# onionboard.net
KiCad netlist of a schematic drawn in EAGLE
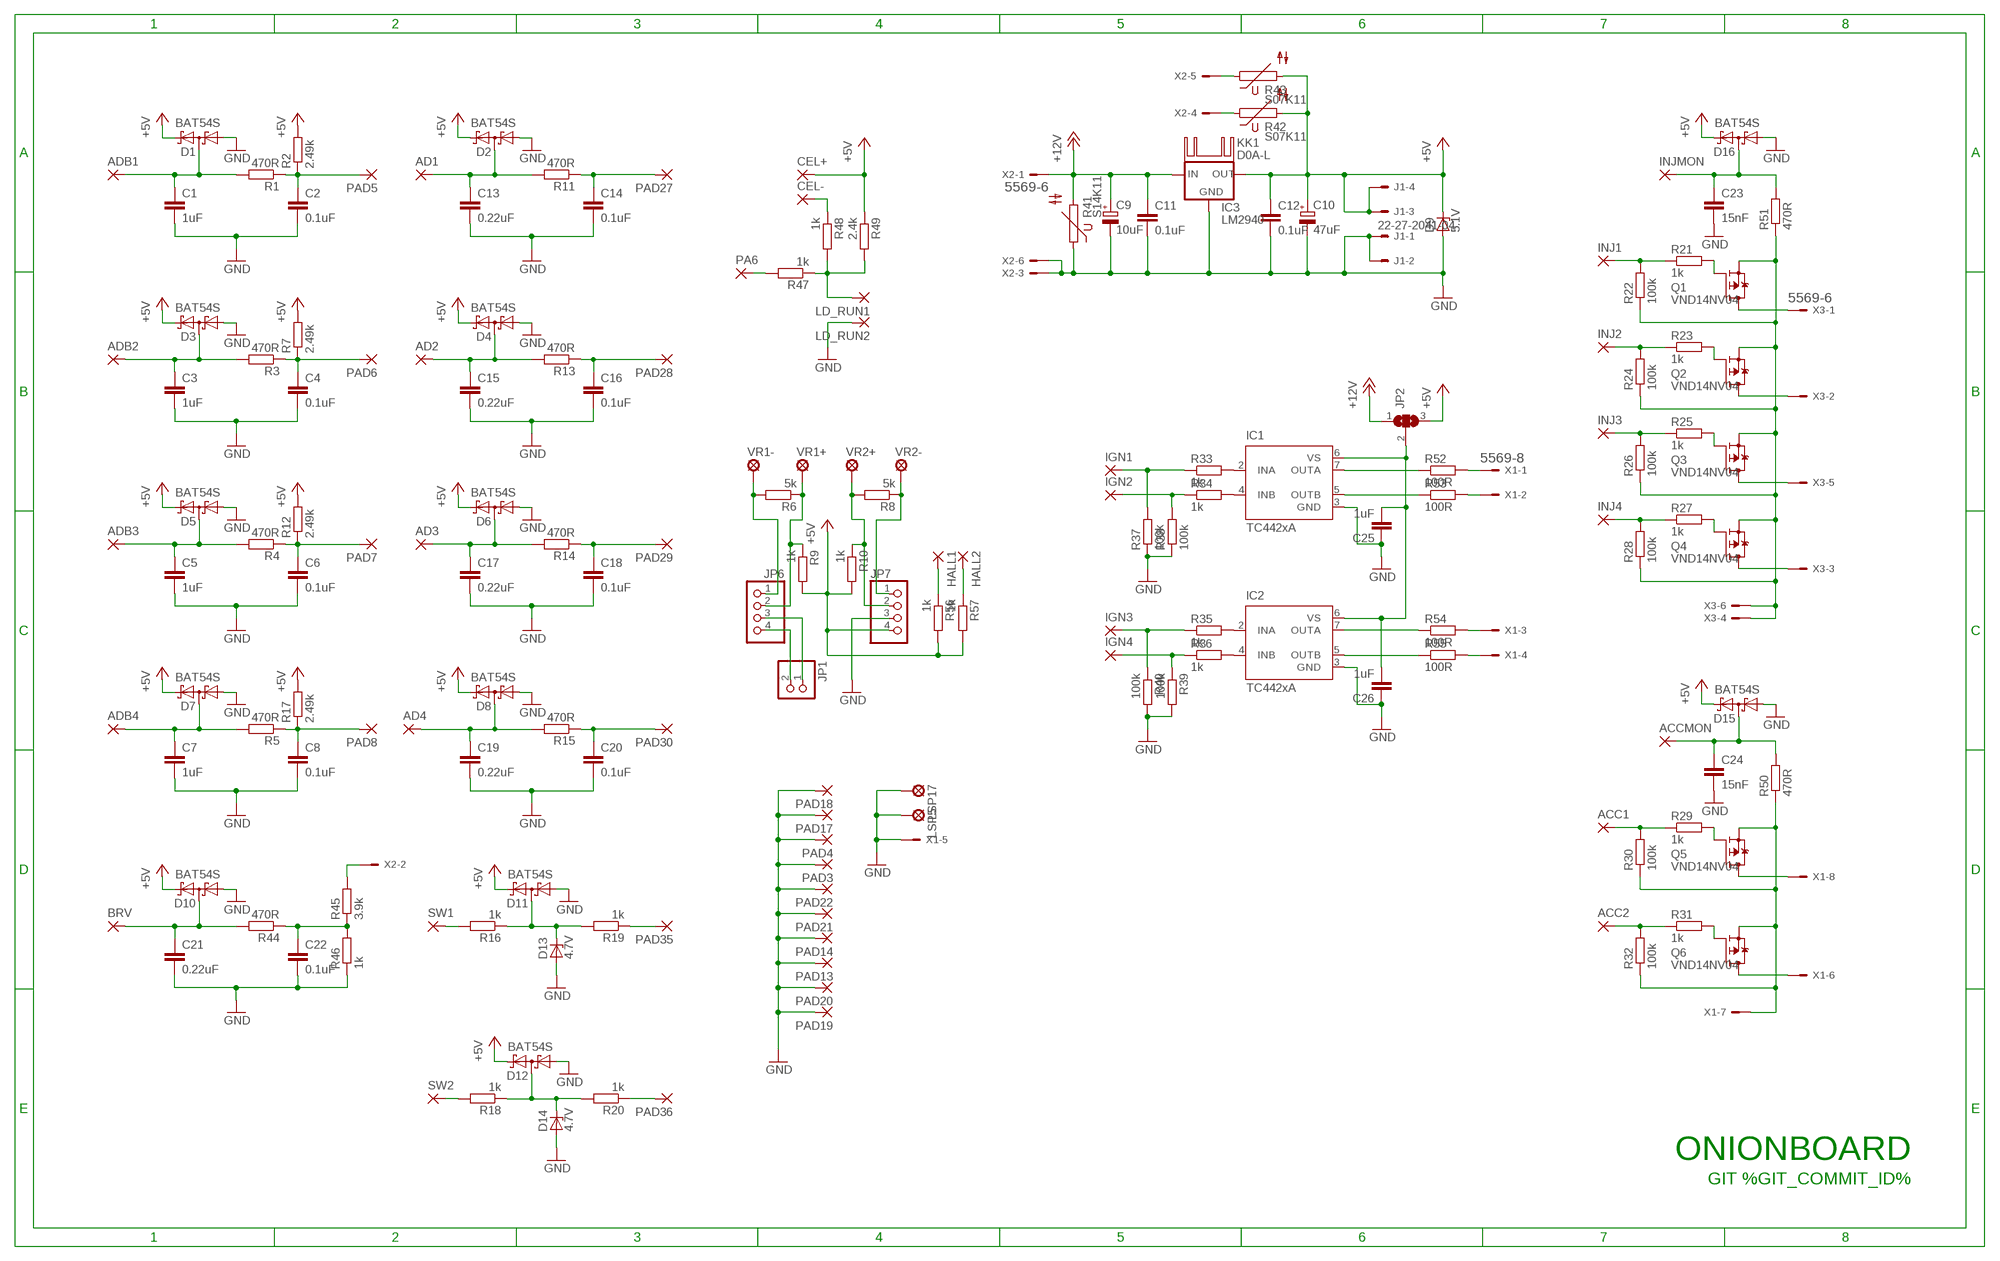
[diagram p0: schematic, sheet 1]

(export (version "E")
  (design (tool "Eeschema 10.0.6"))
  (components
    (comp (ref "ACC1")
      (value "SMD2")
      (footprint "eagle-import:SMD1,27-2,54")
      (libsource (lib "eagle-import") (part "SMD2"))
    )
    (comp (ref "ACC2")
      (value "SMD2")
      (footprint "eagle-import:SMD1,27-2,54")
      (libsource (lib "eagle-import") (part "SMD2"))
    )
    (comp (ref "ACCMON")
      (value "SMD2")
      (footprint "eagle-import:SMD1,27-2,54")
      (libsource (lib "eagle-import") (part "SMD2"))
    )
    (comp (ref "AD1")
      (value "SMD2")
      (footprint "eagle-import:SMD1,27-2,54")
      (libsource (lib "eagle-import") (part "SMD2"))
    )
    (comp (ref "AD2")
      (value "SMD2")
      (footprint "eagle-import:SMD1,27-2,54")
      (libsource (lib "eagle-import") (part "SMD2"))
    )
    (comp (ref "AD3")
      (value "SMD2")
      (footprint "eagle-import:SMD1,27-2,54")
      (libsource (lib "eagle-import") (part "SMD2"))
    )
    (comp (ref "AD4")
      (value "SMD2")
      (footprint "eagle-import:SMD1,27-2,54")
      (libsource (lib "eagle-import") (part "SMD2"))
    )
    (comp (ref "ADB1")
      (value "SMD2")
      (footprint "eagle-import:SMD1,27-2,54")
      (libsource (lib "eagle-import") (part "SMD2"))
    )
    (comp (ref "ADB2")
      (value "SMD2")
      (footprint "eagle-import:SMD1,27-2,54")
      (libsource (lib "eagle-import") (part "SMD2"))
    )
    (comp (ref "ADB3")
      (value "SMD2")
      (footprint "eagle-import:SMD1,27-2,54")
      (libsource (lib "eagle-import") (part "SMD2"))
    )
    (comp (ref "ADB4")
      (value "SMD2")
      (footprint "eagle-import:SMD1,27-2,54")
      (libsource (lib "eagle-import") (part "SMD2"))
    )
    (comp (ref "BRV")
      (value "SMD2")
      (footprint "eagle-import:SMD1,27-2,54")
      (libsource (lib "eagle-import") (part "SMD2"))
    )
    (comp (ref "C1")
      (value "1uF")
      (footprint "eagle-import:C0805")
      (libsource (lib "eagle-import") (part "C-EUC0805"))
    )
    (comp (ref "C2")
      (value "0.1uF")
      (footprint "eagle-import:C0805")
      (libsource (lib "eagle-import") (part "C-EUC0805"))
    )
    (comp (ref "C3")
      (value "1uF")
      (footprint "eagle-import:C0805")
      (libsource (lib "eagle-import") (part "C-EUC0805"))
    )
    (comp (ref "C4")
      (value "0.1uF")
      (footprint "eagle-import:C0805")
      (libsource (lib "eagle-import") (part "C-EUC0805"))
    )
    (comp (ref "C5")
      (value "1uF")
      (footprint "eagle-import:C0805")
      (libsource (lib "eagle-import") (part "C-EUC0805"))
    )
    (comp (ref "C6")
      (value "0.1uF")
      (footprint "eagle-import:C0805")
      (libsource (lib "eagle-import") (part "C-EUC0805"))
    )
    (comp (ref "C7")
      (value "1uF")
      (footprint "eagle-import:C0805")
      (libsource (lib "eagle-import") (part "C-EUC0805"))
    )
    (comp (ref "C8")
      (value "0.1uF")
      (footprint "eagle-import:C0805")
      (libsource (lib "eagle-import") (part "C-EUC0805"))
    )
    (comp (ref "C9")
      (value "10uF")
      (footprint "eagle-import:SMC_E")
      (libsource (lib "eagle-import") (part "CPOL-EUSMCE"))
    )
    (comp (ref "C10")
      (value "47uF")
      (footprint "eagle-import:SMC_E")
      (libsource (lib "eagle-import") (part "CPOL-EUSMCE"))
    )
    (comp (ref "C11")
      (value "0.1uF")
      (footprint "eagle-import:C1206")
      (libsource (lib "eagle-import") (part "C-EUC1206"))
    )
    (comp (ref "C12")
      (value "0.1uF")
      (footprint "eagle-import:C1206")
      (libsource (lib "eagle-import") (part "C-EUC1206"))
    )
    (comp (ref "C13")
      (value "0.22uF")
      (footprint "eagle-import:C0805")
      (libsource (lib "eagle-import") (part "C-EUC0805"))
    )
    (comp (ref "C14")
      (value "0.1uF")
      (footprint "eagle-import:C0805")
      (libsource (lib "eagle-import") (part "C-EUC0805"))
    )
    (comp (ref "C15")
      (value "0.22uF")
      (footprint "eagle-import:C0805")
      (libsource (lib "eagle-import") (part "C-EUC0805"))
    )
    (comp (ref "C16")
      (value "0.1uF")
      (footprint "eagle-import:C0805")
      (libsource (lib "eagle-import") (part "C-EUC0805"))
    )
    (comp (ref "C17")
      (value "0.22uF")
      (footprint "eagle-import:C0805")
      (libsource (lib "eagle-import") (part "C-EUC0805"))
    )
    (comp (ref "C18")
      (value "0.1uF")
      (footprint "eagle-import:C0805")
      (libsource (lib "eagle-import") (part "C-EUC0805"))
    )
    (comp (ref "C19")
      (value "0.22uF")
      (footprint "eagle-import:C0805")
      (libsource (lib "eagle-import") (part "C-EUC0805"))
    )
    (comp (ref "C20")
      (value "0.1uF")
      (footprint "eagle-import:C0805")
      (libsource (lib "eagle-import") (part "C-EUC0805"))
    )
    (comp (ref "C21")
      (value "0.22uF")
      (footprint "eagle-import:C0805")
      (libsource (lib "eagle-import") (part "C-EUC0805"))
    )
    (comp (ref "C22")
      (value "0.1uF")
      (footprint "eagle-import:C0805")
      (libsource (lib "eagle-import") (part "C-EUC0805"))
    )
    (comp (ref "C23")
      (value "15nF")
      (footprint "eagle-import:C0805")
      (libsource (lib "eagle-import") (part "C-EUC0805"))
    )
    (comp (ref "C24")
      (value "15nF")
      (footprint "eagle-import:C0805")
      (libsource (lib "eagle-import") (part "C-EUC0805"))
    )
    (comp (ref "C25")
      (value "1uF")
      (footprint "eagle-import:C1206")
      (libsource (lib "eagle-import") (part "C-EUC1206"))
    )
    (comp (ref "C26")
      (value "1uF")
      (footprint "eagle-import:C1206")
      (libsource (lib "eagle-import") (part "C-EUC1206"))
    )
    (comp (ref "CEL+")
      (value "SMD2")
      (footprint "eagle-import:SMD1,27-2,54")
      (libsource (lib "eagle-import") (part "SMD2"))
    )
    (comp (ref "CEL-")
      (value "SMD2")
      (footprint "eagle-import:SMD1,27-2,54")
      (libsource (lib "eagle-import") (part "SMD2"))
    )
    (comp (ref "D1")
      (value "BAT54S")
      (footprint "eagle-import:SOT23")
      (libsource (lib "eagle-import") (part "BAT54S"))
    )
    (comp (ref "D2")
      (value "BAT54S")
      (footprint "eagle-import:SOT23")
      (libsource (lib "eagle-import") (part "BAT54S"))
    )
    (comp (ref "D3")
      (value "BAT54S")
      (footprint "eagle-import:SOT23")
      (libsource (lib "eagle-import") (part "BAT54S"))
    )
    (comp (ref "D4")
      (value "BAT54S")
      (footprint "eagle-import:SOT23")
      (libsource (lib "eagle-import") (part "BAT54S"))
    )
    (comp (ref "D5")
      (value "BAT54S")
      (footprint "eagle-import:SOT23")
      (libsource (lib "eagle-import") (part "BAT54S"))
    )
    (comp (ref "D6")
      (value "BAT54S")
      (footprint "eagle-import:SOT23")
      (libsource (lib "eagle-import") (part "BAT54S"))
    )
    (comp (ref "D7")
      (value "BAT54S")
      (footprint "eagle-import:SOT23")
      (libsource (lib "eagle-import") (part "BAT54S"))
    )
    (comp (ref "D8")
      (value "BAT54S")
      (footprint "eagle-import:SOT23")
      (libsource (lib "eagle-import") (part "BAT54S"))
    )
    (comp (ref "D9")
      (value "5.1V")
      (footprint "eagle-import:P1Z12")
      (libsource (lib "eagle-import") (part "ZENER-DIODEP1-12"))
    )
    (comp (ref "D10")
      (value "BAT54S")
      (footprint "eagle-import:SOT23")
      (libsource (lib "eagle-import") (part "BAT54S"))
    )
    (comp (ref "D11")
      (value "BAT54S")
      (footprint "eagle-import:SOT23")
      (libsource (lib "eagle-import") (part "BAT54S"))
    )
    (comp (ref "D12")
      (value "BAT54S")
      (footprint "eagle-import:SOT23")
      (libsource (lib "eagle-import") (part "BAT54S"))
    )
    (comp (ref "D13")
      (value "4.7V")
      (footprint "eagle-import:SOT23")
      (libsource (lib "eagle-import") (part "ZENER-DIODESOT23"))
    )
    (comp (ref "D14")
      (value "4.7V")
      (footprint "eagle-import:SOT23")
      (libsource (lib "eagle-import") (part "ZENER-DIODESOT23"))
    )
    (comp (ref "D15")
      (value "BAT54S")
      (footprint "eagle-import:SOT23")
      (libsource (lib "eagle-import") (part "BAT54S"))
    )
    (comp (ref "D16")
      (value "BAT54S")
      (footprint "eagle-import:SOT23")
      (libsource (lib "eagle-import") (part "BAT54S"))
    )
    (comp (ref "HALL1")
      (value "1,6/0,8")
      (footprint "eagle-import:1,6_0,8")
      (libsource (lib "eagle-import") (part "1,6/0,8"))
    )
    (comp (ref "HALL2")
      (value "1,6/0,8")
      (footprint "eagle-import:1,6_0,8")
      (libsource (lib "eagle-import") (part "1,6/0,8"))
    )
    (comp (ref "IC1")
      (value "TC442xA")
      (footprint "eagle-import:SO08")
      (fields (field (name "MF") "INTERNATIONAL RECTIFIER(IR)") (field (name "MPN") "IR4427STRPBF"))
      (libsource (lib "eagle-import") (part "IR4427S"))
    )
    (comp (ref "IC2")
      (value "TC442xA")
      (footprint "eagle-import:SO08")
      (fields (field (name "MF") "INTERNATIONAL RECTIFIER(IR)") (field (name "MPN") "IR4427STRPBF"))
      (libsource (lib "eagle-import") (part "IR4427S"))
    )
    (comp (ref "IC3")
      (value "LM2940")
      (footprint "eagle-import:78XXL")
      (libsource (lib "eagle-import") (part "78XXL"))
    )
    (comp (ref "IGN1")
      (value "SMD2")
      (footprint "eagle-import:SMD1,27-2,54")
      (libsource (lib "eagle-import") (part "SMD2"))
    )
    (comp (ref "IGN2")
      (value "SMD2")
      (footprint "eagle-import:SMD1,27-2,54")
      (libsource (lib "eagle-import") (part "SMD2"))
    )
    (comp (ref "IGN3")
      (value "SMD2")
      (footprint "eagle-import:SMD1,27-2,54")
      (libsource (lib "eagle-import") (part "SMD2"))
    )
    (comp (ref "IGN4")
      (value "SMD2")
      (footprint "eagle-import:SMD1,27-2,54")
      (libsource (lib "eagle-import") (part "SMD2"))
    )
    (comp (ref "INJ1")
      (value "SMD2")
      (footprint "eagle-import:SMD1,27-2,54")
      (libsource (lib "eagle-import") (part "SMD2"))
    )
    (comp (ref "INJ2")
      (value "SMD2")
      (footprint "eagle-import:SMD1,27-2,54")
      (libsource (lib "eagle-import") (part "SMD2"))
    )
    (comp (ref "INJ3")
      (value "SMD2")
      (footprint "eagle-import:SMD1,27-2,54")
      (libsource (lib "eagle-import") (part "SMD2"))
    )
    (comp (ref "INJ4")
      (value "SMD2")
      (footprint "eagle-import:SMD1,27-2,54")
      (libsource (lib "eagle-import") (part "SMD2"))
    )
    (comp (ref "INJMON")
      (value "SMD2")
      (footprint "eagle-import:SMD1,27-2,54")
      (libsource (lib "eagle-import") (part "SMD2"))
    )
    (comp (ref "J1")
      (value "22-27-2041-04")
      (footprint "eagle-import:6410-04")
      (libsource (lib "eagle-import") (part "22-?-0427-2041"))
    )
    (comp (ref "JP1")
      (value "PINHD-1X2")
      (footprint "eagle-import:1X02")
      (libsource (lib "eagle-import") (part "PINHD-1X2"))
    )
    (comp (ref "JP2")
      (value "SJ2W")
      (footprint "eagle-import:SJ_2")
      (libsource (lib "eagle-import") (part "SJ2W"))
    )
    (comp (ref "JP6")
      (value "PINHD-1X4")
      (footprint "eagle-import:1X04")
      (libsource (lib "eagle-import") (part "PINHD-1X4"))
    )
    (comp (ref "JP7")
      (value "PINHD-1X4")
      (footprint "eagle-import:1X04")
      (libsource (lib "eagle-import") (part "PINHD-1X4"))
    )
    (comp (ref "KK1")
      (value "D0A-L")
      (footprint "eagle-import:D02A-L")
      (libsource (lib "eagle-import") (part "D0A-L"))
    )
    (comp (ref "LD_RUN1")
      (value "SMD2")
      (footprint "eagle-import:SMD1,27-2,54")
      (libsource (lib "eagle-import") (part "SMD2"))
    )
    (comp (ref "LD_RUN2")
      (value "SMD2")
      (footprint "eagle-import:SMD1,27-2,54")
      (libsource (lib "eagle-import") (part "SMD2"))
    )
    (comp (ref "LSP5")
      (value "LSP10")
      (footprint "eagle-import:LSP10")
      (libsource (lib "eagle-import") (part "LSP10"))
    )
    (comp (ref "LSP17")
      (value "LSP10")
      (footprint "eagle-import:LSP10")
      (libsource (lib "eagle-import") (part "LSP10"))
    )
    (comp (ref "PA6")
      (value "SMD2")
      (footprint "eagle-import:SMD1,27-2,54")
      (libsource (lib "eagle-import") (part "SMD2"))
    )
    (comp (ref "PAD3")
      (value "SMD2")
      (footprint "eagle-import:SMD1,27-2,54")
      (libsource (lib "eagle-import") (part "SMD2"))
    )
    (comp (ref "PAD4")
      (value "SMD2")
      (footprint "eagle-import:SMD1,27-2,54")
      (libsource (lib "eagle-import") (part "SMD2"))
    )
    (comp (ref "PAD5")
      (value "SMD2")
      (footprint "eagle-import:SMD1,27-2,54")
      (libsource (lib "eagle-import") (part "SMD2"))
    )
    (comp (ref "PAD6")
      (value "SMD2")
      (footprint "eagle-import:SMD1,27-2,54")
      (libsource (lib "eagle-import") (part "SMD2"))
    )
    (comp (ref "PAD7")
      (value "SMD2")
      (footprint "eagle-import:SMD1,27-2,54")
      (libsource (lib "eagle-import") (part "SMD2"))
    )
    (comp (ref "PAD8")
      (value "SMD2")
      (footprint "eagle-import:SMD1,27-2,54")
      (libsource (lib "eagle-import") (part "SMD2"))
    )
    (comp (ref "PAD13")
      (value "SMD2")
      (footprint "eagle-import:SMD1,27-2,54")
      (libsource (lib "eagle-import") (part "SMD2"))
    )
    (comp (ref "PAD14")
      (value "SMD2")
      (footprint "eagle-import:SMD1,27-2,54")
      (libsource (lib "eagle-import") (part "SMD2"))
    )
    (comp (ref "PAD17")
      (value "SMD2")
      (footprint "eagle-import:SMD1,27-2,54")
      (libsource (lib "eagle-import") (part "SMD2"))
    )
    (comp (ref "PAD18")
      (value "SMD2")
      (footprint "eagle-import:SMD1,27-2,54")
      (libsource (lib "eagle-import") (part "SMD2"))
    )
    (comp (ref "PAD19")
      (value "SMD2")
      (footprint "eagle-import:SMD1,27-2,54")
      (libsource (lib "eagle-import") (part "SMD2"))
    )
    (comp (ref "PAD20")
      (value "SMD2")
      (footprint "eagle-import:SMD1,27-2,54")
      (libsource (lib "eagle-import") (part "SMD2"))
    )
    (comp (ref "PAD21")
      (value "SMD2")
      (footprint "eagle-import:SMD1,27-2,54")
      (libsource (lib "eagle-import") (part "SMD2"))
    )
    (comp (ref "PAD22")
      (value "SMD2")
      (footprint "eagle-import:SMD1,27-2,54")
      (libsource (lib "eagle-import") (part "SMD2"))
    )
    (comp (ref "PAD27")
      (value "SMD2")
      (footprint "eagle-import:SMD1,27-2,54")
      (libsource (lib "eagle-import") (part "SMD2"))
    )
    (comp (ref "PAD28")
      (value "SMD2")
      (footprint "eagle-import:SMD1,27-2,54")
      (libsource (lib "eagle-import") (part "SMD2"))
    )
    (comp (ref "PAD29")
      (value "SMD2")
      (footprint "eagle-import:SMD1,27-2,54")
      (libsource (lib "eagle-import") (part "SMD2"))
    )
    (comp (ref "PAD30")
      (value "SMD2")
      (footprint "eagle-import:SMD1,27-2,54")
      (libsource (lib "eagle-import") (part "SMD2"))
    )
    (comp (ref "PAD35")
      (value "SMD2")
      (footprint "eagle-import:SMD1,27-2,54")
      (libsource (lib "eagle-import") (part "SMD2"))
    )
    (comp (ref "PAD36")
      (value "SMD2")
      (footprint "eagle-import:SMD1,27-2,54")
      (libsource (lib "eagle-import") (part "SMD2"))
    )
    (comp (ref "Q1")
      (value "VND14NV04")
      (footprint "eagle-import:TO252")
      (libsource (lib "eagle-import") (part "FDD4141TO252"))
    )
    (comp (ref "Q2")
      (value "VND14NV04")
      (footprint "eagle-import:TO252")
      (libsource (lib "eagle-import") (part "FDD4141TO252"))
    )
    (comp (ref "Q3")
      (value "VND14NV04")
      (footprint "eagle-import:TO252")
      (libsource (lib "eagle-import") (part "FDD4141TO252"))
    )
    (comp (ref "Q4")
      (value "VND14NV04")
      (footprint "eagle-import:TO252")
      (libsource (lib "eagle-import") (part "FDD4141TO252"))
    )
    (comp (ref "Q5")
      (value "VND14NV04")
      (footprint "eagle-import:TO252")
      (libsource (lib "eagle-import") (part "FDD4141TO252"))
    )
    (comp (ref "Q6")
      (value "VND14NV04")
      (footprint "eagle-import:TO252")
      (libsource (lib "eagle-import") (part "FDD4141TO252"))
    )
    (comp (ref "R1")
      (value "470R")
      (footprint "eagle-import:R1206")
      (libsource (lib "eagle-import") (part "R-EU_R1206"))
    )
    (comp (ref "R2")
      (value "2.49k")
      (footprint "eagle-import:M0805")
      (libsource (lib "eagle-import") (part "R-EU_M0805"))
    )
    (comp (ref "R3")
      (value "470R")
      (footprint "eagle-import:R1206")
      (libsource (lib "eagle-import") (part "R-EU_R1206"))
    )
    (comp (ref "R4")
      (value "470R")
      (footprint "eagle-import:R1206")
      (libsource (lib "eagle-import") (part "R-EU_R1206"))
    )
    (comp (ref "R5")
      (value "470R")
      (footprint "eagle-import:R1206")
      (libsource (lib "eagle-import") (part "R-EU_R1206"))
    )
    (comp (ref "R6")
      (value "5k")
      (footprint "eagle-import:0411_15")
      (libsource (lib "eagle-import") (part "R-EU_0411/15"))
    )
    (comp (ref "R7")
      (value "2.49k")
      (footprint "eagle-import:M0805")
      (libsource (lib "eagle-import") (part "R-EU_M0805"))
    )
    (comp (ref "R8")
      (value "5k")
      (footprint "eagle-import:0411_15")
      (libsource (lib "eagle-import") (part "R-EU_0411/15"))
    )
    (comp (ref "R9")
      (value "1k")
      (footprint "eagle-import:R0805")
      (libsource (lib "eagle-import") (part "R-EU_R0805"))
    )
    (comp (ref "R10")
      (value "1k")
      (footprint "eagle-import:R0805")
      (libsource (lib "eagle-import") (part "R-EU_R0805"))
    )
    (comp (ref "R11")
      (value "470R")
      (footprint "eagle-import:R1206")
      (libsource (lib "eagle-import") (part "R-EU_R1206"))
    )
    (comp (ref "R12")
      (value "2.49k")
      (footprint "eagle-import:M0805")
      (libsource (lib "eagle-import") (part "R-EU_M0805"))
    )
    (comp (ref "R13")
      (value "470R")
      (footprint "eagle-import:R1206")
      (libsource (lib "eagle-import") (part "R-EU_R1206"))
    )
    (comp (ref "R14")
      (value "470R")
      (footprint "eagle-import:R1206")
      (libsource (lib "eagle-import") (part "R-EU_R1206"))
    )
    (comp (ref "R15")
      (value "470R")
      (footprint "eagle-import:R1206")
      (libsource (lib "eagle-import") (part "R-EU_R1206"))
    )
    (comp (ref "R16")
      (value "1k")
      (footprint "eagle-import:R1206")
      (libsource (lib "eagle-import") (part "R-EU_R1206"))
    )
    (comp (ref "R17")
      (value "2.49k")
      (footprint "eagle-import:M0805")
      (libsource (lib "eagle-import") (part "R-EU_M0805"))
    )
    (comp (ref "R18")
      (value "1k")
      (footprint "eagle-import:R1206")
      (libsource (lib "eagle-import") (part "R-EU_R1206"))
    )
    (comp (ref "R19")
      (value "1k")
      (footprint "eagle-import:R1206")
      (libsource (lib "eagle-import") (part "R-EU_R1206"))
    )
    (comp (ref "R20")
      (value "1k")
      (footprint "eagle-import:R1206")
      (libsource (lib "eagle-import") (part "R-EU_R1206"))
    )
    (comp (ref "R21")
      (value "1k")
      (footprint "eagle-import:M0805")
      (libsource (lib "eagle-import") (part "R-EU_M0805"))
    )
    (comp (ref "R22")
      (value "100k")
      (footprint "eagle-import:M0805")
      (libsource (lib "eagle-import") (part "R-EU_M0805"))
    )
    (comp (ref "R23")
      (value "1k")
      (footprint "eagle-import:M0805")
      (libsource (lib "eagle-import") (part "R-EU_M0805"))
    )
    (comp (ref "R24")
      (value "100k")
      (footprint "eagle-import:M0805")
      (libsource (lib "eagle-import") (part "R-EU_M0805"))
    )
    (comp (ref "R25")
      (value "1k")
      (footprint "eagle-import:M0805")
      (libsource (lib "eagle-import") (part "R-EU_M0805"))
    )
    (comp (ref "R26")
      (value "100k")
      (footprint "eagle-import:M0805")
      (libsource (lib "eagle-import") (part "R-EU_M0805"))
    )
    (comp (ref "R27")
      (value "1k")
      (footprint "eagle-import:M0805")
      (libsource (lib "eagle-import") (part "R-EU_M0805"))
    )
    (comp (ref "R28")
      (value "100k")
      (footprint "eagle-import:M0805")
      (libsource (lib "eagle-import") (part "R-EU_M0805"))
    )
    (comp (ref "R29")
      (value "1k")
      (footprint "eagle-import:M0805")
      (libsource (lib "eagle-import") (part "R-EU_M0805"))
    )
    (comp (ref "R30")
      (value "100k")
      (footprint "eagle-import:M0805")
      (libsource (lib "eagle-import") (part "R-EU_M0805"))
    )
    (comp (ref "R31")
      (value "1k")
      (footprint "eagle-import:M0805")
      (libsource (lib "eagle-import") (part "R-EU_M0805"))
    )
    (comp (ref "R32")
      (value "100k")
      (footprint "eagle-import:M0805")
      (libsource (lib "eagle-import") (part "R-EU_M0805"))
    )
    (comp (ref "R33")
      (value "1k")
      (footprint "eagle-import:M0805")
      (libsource (lib "eagle-import") (part "R-EU_M0805"))
    )
    (comp (ref "R34")
      (value "1k")
      (footprint "eagle-import:M0805")
      (libsource (lib "eagle-import") (part "R-EU_M0805"))
    )
    (comp (ref "R35")
      (value "1k")
      (footprint "eagle-import:M0805")
      (libsource (lib "eagle-import") (part "R-EU_M0805"))
    )
    (comp (ref "R36")
      (value "1k")
      (footprint "eagle-import:M0805")
      (libsource (lib "eagle-import") (part "R-EU_M0805"))
    )
    (comp (ref "R37")
      (value "100k")
      (footprint "eagle-import:M0805")
      (libsource (lib "eagle-import") (part "R-EU_M0805"))
    )
    (comp (ref "R38")
      (value "100k")
      (footprint "eagle-import:M0805")
      (libsource (lib "eagle-import") (part "R-EU_M0805"))
    )
    (comp (ref "R39")
      (value "100k")
      (footprint "eagle-import:M0805")
      (libsource (lib "eagle-import") (part "R-EU_M0805"))
    )
    (comp (ref "R40")
      (value "100k")
      (footprint "eagle-import:M0805")
      (libsource (lib "eagle-import") (part "R-EU_M0805"))
    )
    (comp (ref "R41")
      (value "S14K11")
      (footprint "eagle-import:S14K11")
      (libsource (lib "eagle-import") (part "S14K11"))
    )
    (comp (ref "R42")
      (value "S07K11")
      (footprint "eagle-import:S07K11")
      (libsource (lib "eagle-import") (part "S07K11"))
    )
    (comp (ref "R43")
      (value "S07K11")
      (footprint "eagle-import:S07K11")
      (libsource (lib "eagle-import") (part "S07K11"))
    )
    (comp (ref "R44")
      (value "470R")
      (footprint "eagle-import:R1206")
      (libsource (lib "eagle-import") (part "R-EU_R1206"))
    )
    (comp (ref "R45")
      (value "3.9k")
      (footprint "eagle-import:M0805")
      (libsource (lib "eagle-import") (part "R-EU_M0805"))
    )
    (comp (ref "R46")
      (value "1k")
      (footprint "eagle-import:M0805")
      (libsource (lib "eagle-import") (part "R-EU_M0805"))
    )
    (comp (ref "R47")
      (value "1k")
      (footprint "eagle-import:M0805")
      (libsource (lib "eagle-import") (part "R-EU_M0805"))
    )
    (comp (ref "R48")
      (value "1k")
      (footprint "eagle-import:M0805")
      (libsource (lib "eagle-import") (part "R-EU_M0805"))
    )
    (comp (ref "R49")
      (value "2.4k")
      (footprint "eagle-import:M0805")
      (libsource (lib "eagle-import") (part "R-EU_M0805"))
    )
    (comp (ref "R50")
      (value "470R")
      (footprint "eagle-import:R1206")
      (libsource (lib "eagle-import") (part "R-EU_R1206"))
    )
    (comp (ref "R51")
      (value "470R")
      (footprint "eagle-import:R1206")
      (libsource (lib "eagle-import") (part "R-EU_R1206"))
    )
    (comp (ref "R52")
      (value "100R")
      (footprint "eagle-import:0414V")
      (libsource (lib "eagle-import") (part "R-EU_0414/5V"))
    )
    (comp (ref "R53")
      (value "100R")
      (footprint "eagle-import:0414V")
      (libsource (lib "eagle-import") (part "R-EU_0414/5V"))
    )
    (comp (ref "R54")
      (value "100R")
      (footprint "eagle-import:0414V")
      (libsource (lib "eagle-import") (part "R-EU_0414/5V"))
    )
    (comp (ref "R55")
      (value "100R")
      (footprint "eagle-import:0414V")
      (libsource (lib "eagle-import") (part "R-EU_0414/5V"))
    )
    (comp (ref "R56")
      (value "1k")
      (footprint "eagle-import:R0805")
      (libsource (lib "eagle-import") (part "R-EU_R0805"))
    )
    (comp (ref "R57")
      (value "1k")
      (footprint "eagle-import:R0805")
      (libsource (lib "eagle-import") (part "R-EU_R0805"))
    )
    (comp (ref "SW1")
      (value "SMD2")
      (footprint "eagle-import:SMD1,27-2,54")
      (libsource (lib "eagle-import") (part "SMD2"))
    )
    (comp (ref "SW2")
      (value "SMD2")
      (footprint "eagle-import:SMD1,27-2,54")
      (libsource (lib "eagle-import") (part "SMD2"))
    )
    (comp (ref "VR1+")
      (value "LSP10")
      (footprint "eagle-import:LSP10")
      (libsource (lib "eagle-import") (part "LSP10"))
    )
    (comp (ref "VR1-")
      (value "LSP10")
      (footprint "eagle-import:LSP10")
      (libsource (lib "eagle-import") (part "LSP10"))
    )
    (comp (ref "VR2+")
      (value "LSP10")
      (footprint "eagle-import:LSP10")
      (libsource (lib "eagle-import") (part "LSP10"))
    )
    (comp (ref "VR2-")
      (value "LSP10")
      (footprint "eagle-import:LSP10")
      (libsource (lib "eagle-import") (part "LSP10"))
    )
    (comp (ref "X1")
      (value "5569-8")
      (footprint "eagle-import:5569-8")
      (libsource (lib "eagle-import") (part "5569-8"))
    )
    (comp (ref "X2")
      (value "5569-6")
      (footprint "eagle-import:5569-6")
      (libsource (lib "eagle-import") (part "5569-6"))
    )
    (comp (ref "X3")
      (value "5569-6")
      (footprint "eagle-import:5569-6")
      (libsource (lib "eagle-import") (part "5569-6"))
    )
  )
  (nets
    (net (code "1") (name "+5V") (class "Default")
      (node (ref "C10") (pin "+") (pinfunction "+_+") (pintype "passive"))
      (node (ref "C12") (pin "1") (pinfunction "1_1") (pintype "passive"))
      (node (ref "CEL+") (pin "1") (pinfunction "P_1") (pintype "passive"))
      (node (ref "D1") (pin "2") (pinfunction "C2_2") (pintype "passive"))
      (node (ref "D10") (pin "2") (pinfunction "C2_2") (pintype "passive"))
      (node (ref "D11") (pin "2") (pinfunction "C2_2") (pintype "passive"))
      (node (ref "D12") (pin "2") (pinfunction "C2_2") (pintype "passive"))
      (node (ref "D15") (pin "2") (pinfunction "C2_2") (pintype "passive"))
      (node (ref "D16") (pin "2") (pinfunction "C2_2") (pintype "passive"))
      (node (ref "D2") (pin "2") (pinfunction "C2_2") (pintype "passive"))
      (node (ref "D3") (pin "2") (pinfunction "C2_2") (pintype "passive"))
      (node (ref "D4") (pin "2") (pinfunction "C2_2") (pintype "passive"))
      (node (ref "D5") (pin "2") (pinfunction "C2_2") (pintype "passive"))
      (node (ref "D6") (pin "2") (pinfunction "C2_2") (pintype "passive"))
      (node (ref "D7") (pin "2") (pinfunction "C2_2") (pintype "passive"))
      (node (ref "D8") (pin "2") (pinfunction "C2_2") (pintype "passive"))
      (node (ref "D9") (pin "C") (pinfunction "C_C") (pintype "passive"))
      (node (ref "IC3") (pin "OUT") (pinfunction "OUT_OUT") (pintype "passive"))
      (node (ref "J1") (pin "3") (pinfunction "S_3") (pintype "passive"))
      (node (ref "J1") (pin "4") (pinfunction "S_4") (pintype "passive"))
      (node (ref "JP2") (pin "3") (pinfunction "3_3") (pintype "passive"))
      (node (ref "JP7") (pin "4") (pinfunction "4_4") (pintype "passive"))
      (node (ref "R10") (pin "2") (pinfunction "2_2") (pintype "passive"))
      (node (ref "R12") (pin "2") (pinfunction "2_2") (pintype "passive"))
      (node (ref "R17") (pin "2") (pinfunction "2_2") (pintype "passive"))
      (node (ref "R2") (pin "2") (pinfunction "2_2") (pintype "passive"))
      (node (ref "R42") (pin "2") (pinfunction "2_2") (pintype "passive"))
      (node (ref "R43") (pin "2") (pinfunction "2_2") (pintype "passive"))
      (node (ref "R49") (pin "1") (pinfunction "1_1") (pintype "passive"))
      (node (ref "R56") (pin "2") (pinfunction "2_2") (pintype "passive"))
      (node (ref "R57") (pin "2") (pinfunction "2_2") (pintype "passive"))
      (node (ref "R7") (pin "2") (pinfunction "2_2") (pintype "passive"))
      (node (ref "R9") (pin "2") (pinfunction "2_2") (pintype "passive"))
    )
    (net (code "2") (name "+12V") (class "Default")
      (node (ref "C11") (pin "1") (pinfunction "1_1") (pintype "passive"))
      (node (ref "C9") (pin "+") (pinfunction "+_+") (pintype "passive"))
      (node (ref "IC3") (pin "IN") (pinfunction "IN_IN") (pintype "input"))
      (node (ref "JP2") (pin "1") (pinfunction "1_1") (pintype "passive"))
      (node (ref "R41") (pin "2") (pinfunction "2_2") (pintype "passive"))
      (node (ref "X2") (pin "1") (pinfunction ">NAME$_1") (pintype "bidirectional"))
    )
    (net (code "3") (name "GND") (class "Default")
      (node (ref "C1") (pin "2") (pinfunction "2_2") (pintype "passive"))
      (node (ref "C10") (pin "-") (pinfunction "-_-") (pintype "passive"))
      (node (ref "C11") (pin "2") (pinfunction "2_2") (pintype "passive"))
      (node (ref "C12") (pin "2") (pinfunction "2_2") (pintype "passive"))
      (node (ref "C13") (pin "2") (pinfunction "2_2") (pintype "passive"))
      (node (ref "C14") (pin "2") (pinfunction "2_2") (pintype "passive"))
      (node (ref "C15") (pin "2") (pinfunction "2_2") (pintype "passive"))
      (node (ref "C16") (pin "2") (pinfunction "2_2") (pintype "passive"))
      (node (ref "C17") (pin "2") (pinfunction "2_2") (pintype "passive"))
      (node (ref "C18") (pin "2") (pinfunction "2_2") (pintype "passive"))
      (node (ref "C19") (pin "2") (pinfunction "2_2") (pintype "passive"))
      (node (ref "C2") (pin "2") (pinfunction "2_2") (pintype "passive"))
      (node (ref "C20") (pin "2") (pinfunction "2_2") (pintype "passive"))
      (node (ref "C21") (pin "2") (pinfunction "2_2") (pintype "passive"))
      (node (ref "C22") (pin "2") (pinfunction "2_2") (pintype "passive"))
      (node (ref "C23") (pin "2") (pinfunction "2_2") (pintype "passive"))
      (node (ref "C24") (pin "2") (pinfunction "2_2") (pintype "passive"))
      (node (ref "C25") (pin "1") (pinfunction "1_1") (pintype "passive"))
      (node (ref "C26") (pin "1") (pinfunction "1_1") (pintype "passive"))
      (node (ref "C3") (pin "2") (pinfunction "2_2") (pintype "passive"))
      (node (ref "C4") (pin "2") (pinfunction "2_2") (pintype "passive"))
      (node (ref "C5") (pin "2") (pinfunction "2_2") (pintype "passive"))
      (node (ref "C6") (pin "2") (pinfunction "2_2") (pintype "passive"))
      (node (ref "C7") (pin "2") (pinfunction "2_2") (pintype "passive"))
      (node (ref "C8") (pin "2") (pinfunction "2_2") (pintype "passive"))
      (node (ref "C9") (pin "-") (pinfunction "-_-") (pintype "passive"))
      (node (ref "D1") (pin "1") (pinfunction "A1_1") (pintype "passive"))
      (node (ref "D10") (pin "1") (pinfunction "A1_1") (pintype "passive"))
      (node (ref "D11") (pin "1") (pinfunction "A1_1") (pintype "passive"))
      (node (ref "D12") (pin "1") (pinfunction "A1_1") (pintype "passive"))
      (node (ref "D13") (pin "1") (pinfunction "A_1") (pintype "passive"))
      (node (ref "D14") (pin "1") (pinfunction "A_1") (pintype "passive"))
      (node (ref "D15") (pin "1") (pinfunction "A1_1") (pintype "passive"))
      (node (ref "D16") (pin "1") (pinfunction "A1_1") (pintype "passive"))
      (node (ref "D2") (pin "1") (pinfunction "A1_1") (pintype "passive"))
      (node (ref "D3") (pin "1") (pinfunction "A1_1") (pintype "passive"))
      (node (ref "D4") (pin "1") (pinfunction "A1_1") (pintype "passive"))
      (node (ref "D5") (pin "1") (pinfunction "A1_1") (pintype "passive"))
      (node (ref "D6") (pin "1") (pinfunction "A1_1") (pintype "passive"))
      (node (ref "D7") (pin "1") (pinfunction "A1_1") (pintype "passive"))
      (node (ref "D8") (pin "1") (pinfunction "A1_1") (pintype "passive"))
      (node (ref "D9") (pin "A") (pinfunction "A_A") (pintype "passive"))
      (node (ref "IC1") (pin "3") (pinfunction "GND_3") (pintype "power_in"))
      (node (ref "IC2") (pin "3") (pinfunction "GND_3") (pintype "power_in"))
      (node (ref "IC3") (pin "GND") (pinfunction "GND_GND") (pintype "input"))
      (node (ref "J1") (pin "1") (pinfunction "S_1") (pintype "passive"))
      (node (ref "J1") (pin "2") (pinfunction "S_2") (pintype "passive"))
      (node (ref "JP7") (pin "3") (pinfunction "3_3") (pintype "passive"))
      (node (ref "LD_RUN2") (pin "1") (pinfunction "P_1") (pintype "passive"))
      (node (ref "LSP17") (pin "MP") (pinfunction "MP_MP") (pintype "passive"))
      (node (ref "LSP5") (pin "MP") (pinfunction "MP_MP") (pintype "passive"))
      (node (ref "PAD13") (pin "1") (pinfunction "P_1") (pintype "passive"))
      (node (ref "PAD14") (pin "1") (pinfunction "P_1") (pintype "passive"))
      (node (ref "PAD17") (pin "1") (pinfunction "P_1") (pintype "passive"))
      (node (ref "PAD18") (pin "1") (pinfunction "P_1") (pintype "passive"))
      (node (ref "PAD19") (pin "1") (pinfunction "P_1") (pintype "passive"))
      (node (ref "PAD20") (pin "1") (pinfunction "P_1") (pintype "passive"))
      (node (ref "PAD21") (pin "1") (pinfunction "P_1") (pintype "passive"))
      (node (ref "PAD22") (pin "1") (pinfunction "P_1") (pintype "passive"))
      (node (ref "PAD3") (pin "1") (pinfunction "P_1") (pintype "passive"))
      (node (ref "PAD4") (pin "1") (pinfunction "P_1") (pintype "passive"))
      (node (ref "R37") (pin "1") (pinfunction "1_1") (pintype "passive"))
      (node (ref "R38") (pin "1") (pinfunction "1_1") (pintype "passive"))
      (node (ref "R39") (pin "2") (pinfunction "2_2") (pintype "passive"))
      (node (ref "R40") (pin "2") (pinfunction "2_2") (pintype "passive"))
      (node (ref "R41") (pin "1") (pinfunction "1_1") (pintype "passive"))
      (node (ref "R46") (pin "1") (pinfunction "1_1") (pintype "passive"))
      (node (ref "X1") (pin "5") (pinfunction ">NAME$_5") (pintype "bidirectional"))
      (node (ref "X2") (pin "3") (pinfunction ">NAME$_3") (pintype "bidirectional"))
      (node (ref "X2") (pin "6") (pinfunction ">NAME$_6") (pintype "bidirectional"))
    )
    (net (code "4") (name "Net-(ACC1-P)") (class "Default")
      (node (ref "ACC1") (pin "1") (pinfunction "P_1") (pintype "passive"))
      (node (ref "R29") (pin "1") (pinfunction "1_1") (pintype "passive"))
      (node (ref "R30") (pin "2") (pinfunction "2_2") (pintype "passive"))
    )
    (net (code "5") (name "Net-(ACC2-P)") (class "Default")
      (node (ref "ACC2") (pin "1") (pinfunction "P_1") (pintype "passive"))
      (node (ref "R31") (pin "1") (pinfunction "1_1") (pintype "passive"))
      (node (ref "R32") (pin "2") (pinfunction "2_2") (pintype "passive"))
    )
    (net (code "6") (name "Net-(ACCMON-P)") (class "Default")
      (node (ref "ACCMON") (pin "1") (pinfunction "P_1") (pintype "passive"))
      (node (ref "C24") (pin "1") (pinfunction "1_1") (pintype "passive"))
      (node (ref "D15") (pin "3") (pinfunction "C1A2_3") (pintype "passive"))
      (node (ref "R50") (pin "2") (pinfunction "2_2") (pintype "passive"))
    )
    (net (code "7") (name "Net-(AD1-P)") (class "Default")
      (node (ref "AD1") (pin "1") (pinfunction "P_1") (pintype "passive"))
      (node (ref "C13") (pin "1") (pinfunction "1_1") (pintype "passive"))
      (node (ref "D2") (pin "3") (pinfunction "C1A2_3") (pintype "passive"))
      (node (ref "R11") (pin "2") (pinfunction "2_2") (pintype "passive"))
    )
    (net (code "8") (name "Net-(AD2-P)") (class "Default")
      (node (ref "AD2") (pin "1") (pinfunction "P_1") (pintype "passive"))
      (node (ref "C15") (pin "1") (pinfunction "1_1") (pintype "passive"))
      (node (ref "D4") (pin "3") (pinfunction "C1A2_3") (pintype "passive"))
      (node (ref "R13") (pin "2") (pinfunction "2_2") (pintype "passive"))
    )
    (net (code "9") (name "Net-(AD3-P)") (class "Default")
      (node (ref "AD3") (pin "1") (pinfunction "P_1") (pintype "passive"))
      (node (ref "C17") (pin "1") (pinfunction "1_1") (pintype "passive"))
      (node (ref "D6") (pin "3") (pinfunction "C1A2_3") (pintype "passive"))
      (node (ref "R14") (pin "2") (pinfunction "2_2") (pintype "passive"))
    )
    (net (code "10") (name "Net-(AD4-P)") (class "Default")
      (node (ref "AD4") (pin "1") (pinfunction "P_1") (pintype "passive"))
      (node (ref "C19") (pin "1") (pinfunction "1_1") (pintype "passive"))
      (node (ref "D8") (pin "3") (pinfunction "C1A2_3") (pintype "passive"))
      (node (ref "R15") (pin "2") (pinfunction "2_2") (pintype "passive"))
    )
    (net (code "11") (name "Net-(ADB1-P)") (class "Default")
      (node (ref "ADB1") (pin "1") (pinfunction "P_1") (pintype "passive"))
      (node (ref "C1") (pin "1") (pinfunction "1_1") (pintype "passive"))
      (node (ref "D1") (pin "3") (pinfunction "C1A2_3") (pintype "passive"))
      (node (ref "R1") (pin "2") (pinfunction "2_2") (pintype "passive"))
    )
    (net (code "12") (name "Net-(ADB2-P)") (class "Default")
      (node (ref "ADB2") (pin "1") (pinfunction "P_1") (pintype "passive"))
      (node (ref "C3") (pin "1") (pinfunction "1_1") (pintype "passive"))
      (node (ref "D3") (pin "3") (pinfunction "C1A2_3") (pintype "passive"))
      (node (ref "R3") (pin "2") (pinfunction "2_2") (pintype "passive"))
    )
    (net (code "13") (name "Net-(ADB3-P)") (class "Default")
      (node (ref "ADB3") (pin "1") (pinfunction "P_1") (pintype "passive"))
      (node (ref "C5") (pin "1") (pinfunction "1_1") (pintype "passive"))
      (node (ref "D5") (pin "3") (pinfunction "C1A2_3") (pintype "passive"))
      (node (ref "R4") (pin "2") (pinfunction "2_2") (pintype "passive"))
    )
    (net (code "14") (name "Net-(ADB4-P)") (class "Default")
      (node (ref "ADB4") (pin "1") (pinfunction "P_1") (pintype "passive"))
      (node (ref "C7") (pin "1") (pinfunction "1_1") (pintype "passive"))
      (node (ref "D7") (pin "3") (pinfunction "C1A2_3") (pintype "passive"))
      (node (ref "R5") (pin "2") (pinfunction "2_2") (pintype "passive"))
    )
    (net (code "15") (name "Net-(BRV-P)") (class "Default")
      (node (ref "BRV") (pin "1") (pinfunction "P_1") (pintype "passive"))
      (node (ref "C21") (pin "1") (pinfunction "1_1") (pintype "passive"))
      (node (ref "D10") (pin "3") (pinfunction "C1A2_3") (pintype "passive"))
      (node (ref "R44") (pin "2") (pinfunction "2_2") (pintype "passive"))
    )
    (net (code "16") (name "Net-(C22-Pad1)") (class "Default")
      (node (ref "C22") (pin "1") (pinfunction "1_1") (pintype "passive"))
      (node (ref "R44") (pin "1") (pinfunction "1_1") (pintype "passive"))
      (node (ref "R45") (pin "1") (pinfunction "1_1") (pintype "passive"))
      (node (ref "R46") (pin "2") (pinfunction "2_2") (pintype "passive"))
    )
    (net (code "17") (name "Net-(CEL--P)") (class "Default")
      (node (ref "CEL-") (pin "1") (pinfunction "P_1") (pintype "passive"))
      (node (ref "R48") (pin "1") (pinfunction "1_1") (pintype "passive"))
    )
    (net (code "18") (name "Net-(D11-C1A2)") (class "Default")
      (node (ref "D11") (pin "3") (pinfunction "C1A2_3") (pintype "passive"))
      (node (ref "D13") (pin "3") (pinfunction "C_3") (pintype "passive"))
      (node (ref "R16") (pin "1") (pinfunction "1_1") (pintype "passive"))
      (node (ref "R19") (pin "2") (pinfunction "2_2") (pintype "passive"))
    )
    (net (code "19") (name "Net-(D12-C1A2)") (class "Default")
      (node (ref "D12") (pin "3") (pinfunction "C1A2_3") (pintype "passive"))
      (node (ref "D14") (pin "3") (pinfunction "C_3") (pintype "passive"))
      (node (ref "R18") (pin "1") (pinfunction "1_1") (pintype "passive"))
      (node (ref "R20") (pin "2") (pinfunction "2_2") (pintype "passive"))
    )
    (net (code "20") (name "Net-(D16-C1A2)") (class "Default")
      (node (ref "C23") (pin "1") (pinfunction "1_1") (pintype "passive"))
      (node (ref "D16") (pin "3") (pinfunction "C1A2_3") (pintype "passive"))
      (node (ref "INJMON") (pin "1") (pinfunction "P_1") (pintype "passive"))
      (node (ref "R51") (pin "2") (pinfunction "2_2") (pintype "passive"))
    )
    (net (code "21") (name "Net-(HALL1-P)") (class "Default")
      (node (ref "HALL1") (pin "1") (pinfunction "P_1") (pintype "passive"))
      (node (ref "R56") (pin "1") (pinfunction "1_1") (pintype "passive"))
    )
    (net (code "22") (name "Net-(HALL2-P)") (class "Default")
      (node (ref "HALL2") (pin "1") (pinfunction "P_1") (pintype "passive"))
      (node (ref "R57") (pin "1") (pinfunction "1_1") (pintype "passive"))
    )
    (net (code "23") (name "Net-(IC1-INA)") (class "Default")
      (node (ref "IC1") (pin "2") (pinfunction "INA_2") (pintype "input"))
      (node (ref "R33") (pin "2") (pinfunction "2_2") (pintype "passive"))
    )
    (net (code "24") (name "Net-(IC1-INB)") (class "Default")
      (node (ref "IC1") (pin "4") (pinfunction "INB_4") (pintype "input"))
      (node (ref "R34") (pin "2") (pinfunction "2_2") (pintype "passive"))
    )
    (net (code "25") (name "Net-(IC1-OUTA)") (class "Default")
      (node (ref "IC1") (pin "7") (pinfunction "OUTA_7") (pintype "output"))
      (node (ref "R52") (pin "1") (pinfunction "1_1") (pintype "passive"))
    )
    (net (code "26") (name "Net-(IC1-OUTB)") (class "Default")
      (node (ref "IC1") (pin "5") (pinfunction "OUTB_5") (pintype "output"))
      (node (ref "R53") (pin "1") (pinfunction "1_1") (pintype "passive"))
    )
    (net (code "27") (name "Net-(IC1-VS)") (class "Default")
      (node (ref "C25") (pin "2") (pinfunction "2_2") (pintype "passive"))
      (node (ref "C26") (pin "2") (pinfunction "2_2") (pintype "passive"))
      (node (ref "IC1") (pin "6") (pinfunction "VS_6") (pintype "power_in"))
      (node (ref "IC2") (pin "6") (pinfunction "VS_6") (pintype "power_in"))
      (node (ref "JP2") (pin "2") (pinfunction "2_2") (pintype "passive"))
    )
    (net (code "28") (name "Net-(IC2-INA)") (class "Default")
      (node (ref "IC2") (pin "2") (pinfunction "INA_2") (pintype "input"))
      (node (ref "R35") (pin "2") (pinfunction "2_2") (pintype "passive"))
    )
    (net (code "29") (name "Net-(IC2-INB)") (class "Default")
      (node (ref "IC2") (pin "4") (pinfunction "INB_4") (pintype "input"))
      (node (ref "R36") (pin "2") (pinfunction "2_2") (pintype "passive"))
    )
    (net (code "30") (name "Net-(IC2-OUTA)") (class "Default")
      (node (ref "IC2") (pin "7") (pinfunction "OUTA_7") (pintype "output"))
      (node (ref "R54") (pin "1") (pinfunction "1_1") (pintype "passive"))
    )
    (net (code "31") (name "Net-(IC2-OUTB)") (class "Default")
      (node (ref "IC2") (pin "5") (pinfunction "OUTB_5") (pintype "output"))
      (node (ref "R55") (pin "1") (pinfunction "1_1") (pintype "passive"))
    )
    (net (code "32") (name "Net-(IGN1-P)") (class "Default")
      (node (ref "IGN1") (pin "1") (pinfunction "P_1") (pintype "passive"))
      (node (ref "R33") (pin "1") (pinfunction "1_1") (pintype "passive"))
      (node (ref "R37") (pin "2") (pinfunction "2_2") (pintype "passive"))
    )
    (net (code "33") (name "Net-(IGN2-P)") (class "Default")
      (node (ref "IGN2") (pin "1") (pinfunction "P_1") (pintype "passive"))
      (node (ref "R34") (pin "1") (pinfunction "1_1") (pintype "passive"))
      (node (ref "R38") (pin "2") (pinfunction "2_2") (pintype "passive"))
    )
    (net (code "34") (name "Net-(IGN3-P)") (class "Default")
      (node (ref "IGN3") (pin "1") (pinfunction "P_1") (pintype "passive"))
      (node (ref "R35") (pin "1") (pinfunction "1_1") (pintype "passive"))
      (node (ref "R40") (pin "1") (pinfunction "1_1") (pintype "passive"))
    )
    (net (code "35") (name "Net-(IGN4-P)") (class "Default")
      (node (ref "IGN4") (pin "1") (pinfunction "P_1") (pintype "passive"))
      (node (ref "R36") (pin "1") (pinfunction "1_1") (pintype "passive"))
      (node (ref "R39") (pin "1") (pinfunction "1_1") (pintype "passive"))
    )
    (net (code "36") (name "Net-(INJ1-P)") (class "Default")
      (node (ref "INJ1") (pin "1") (pinfunction "P_1") (pintype "passive"))
      (node (ref "R21") (pin "1") (pinfunction "1_1") (pintype "passive"))
      (node (ref "R22") (pin "2") (pinfunction "2_2") (pintype "passive"))
    )
    (net (code "37") (name "Net-(INJ2-P)") (class "Default")
      (node (ref "INJ2") (pin "1") (pinfunction "P_1") (pintype "passive"))
      (node (ref "R23") (pin "1") (pinfunction "1_1") (pintype "passive"))
      (node (ref "R24") (pin "2") (pinfunction "2_2") (pintype "passive"))
    )
    (net (code "38") (name "Net-(INJ3-P)") (class "Default")
      (node (ref "INJ3") (pin "1") (pinfunction "P_1") (pintype "passive"))
      (node (ref "R25") (pin "1") (pinfunction "1_1") (pintype "passive"))
      (node (ref "R26") (pin "2") (pinfunction "2_2") (pintype "passive"))
    )
    (net (code "39") (name "Net-(INJ4-P)") (class "Default")
      (node (ref "INJ4") (pin "1") (pinfunction "P_1") (pintype "passive"))
      (node (ref "R27") (pin "1") (pinfunction "1_1") (pintype "passive"))
      (node (ref "R28") (pin "2") (pinfunction "2_2") (pintype "passive"))
    )
    (net (code "40") (name "Net-(JP1-Pad1)") (class "Default")
      (node (ref "JP1") (pin "1") (pinfunction "1_1") (pintype "passive"))
      (node (ref "JP6") (pin "3") (pinfunction "3_3") (pintype "passive"))
    )
    (net (code "41") (name "Net-(JP1-Pad2)") (class "Default")
      (node (ref "JP1") (pin "2") (pinfunction "2_2") (pintype "passive"))
      (node (ref "JP6") (pin "4") (pinfunction "4_4") (pintype "passive"))
    )
    (net (code "42") (name "Net-(JP6-Pad1)") (class "Default")
      (node (ref "JP6") (pin "1") (pinfunction "1_1") (pintype "passive"))
      (node (ref "R6") (pin "2") (pinfunction "2_2") (pintype "passive"))
      (node (ref "VR1-") (pin "MP") (pinfunction "MP_MP") (pintype "passive"))
    )
    (net (code "43") (name "Net-(JP6-Pad2)") (class "Default")
      (node (ref "JP6") (pin "2") (pinfunction "2_2") (pintype "passive"))
      (node (ref "R6") (pin "1") (pinfunction "1_1") (pintype "passive"))
      (node (ref "R9") (pin "1") (pinfunction "1_1") (pintype "passive"))
      (node (ref "VR1+") (pin "MP") (pinfunction "MP_MP") (pintype "passive"))
    )
    (net (code "44") (name "Net-(JP7-Pad1)") (class "Default")
      (node (ref "JP7") (pin "1") (pinfunction "1_1") (pintype "passive"))
      (node (ref "R8") (pin "1") (pinfunction "1_1") (pintype "passive"))
      (node (ref "VR2-") (pin "MP") (pinfunction "MP_MP") (pintype "passive"))
    )
    (net (code "45") (name "Net-(JP7-Pad2)") (class "Default")
      (node (ref "JP7") (pin "2") (pinfunction "2_2") (pintype "passive"))
      (node (ref "R10") (pin "1") (pinfunction "1_1") (pintype "passive"))
      (node (ref "R8") (pin "2") (pinfunction "2_2") (pintype "passive"))
      (node (ref "VR2+") (pin "MP") (pinfunction "MP_MP") (pintype "passive"))
    )
    (net (code "46") (name "Net-(LD_RUN1-P)") (class "Default")
      (node (ref "LD_RUN1") (pin "1") (pinfunction "P_1") (pintype "passive"))
      (node (ref "R47") (pin "1") (pinfunction "1_1") (pintype "passive"))
      (node (ref "R48") (pin "2") (pinfunction "2_2") (pintype "passive"))
      (node (ref "R49") (pin "2") (pinfunction "2_2") (pintype "passive"))
    )
    (net (code "47") (name "Net-(PA6-P)") (class "Default")
      (node (ref "PA6") (pin "1") (pinfunction "P_1") (pintype "passive"))
      (node (ref "R47") (pin "2") (pinfunction "2_2") (pintype "passive"))
    )
    (net (code "48") (name "Net-(PAD5-P)") (class "Default")
      (node (ref "C2") (pin "1") (pinfunction "1_1") (pintype "passive"))
      (node (ref "PAD5") (pin "1") (pinfunction "P_1") (pintype "passive"))
      (node (ref "R1") (pin "1") (pinfunction "1_1") (pintype "passive"))
      (node (ref "R2") (pin "1") (pinfunction "1_1") (pintype "passive"))
    )
    (net (code "49") (name "Net-(PAD6-P)") (class "Default")
      (node (ref "C4") (pin "1") (pinfunction "1_1") (pintype "passive"))
      (node (ref "PAD6") (pin "1") (pinfunction "P_1") (pintype "passive"))
      (node (ref "R3") (pin "1") (pinfunction "1_1") (pintype "passive"))
      (node (ref "R7") (pin "1") (pinfunction "1_1") (pintype "passive"))
    )
    (net (code "50") (name "Net-(PAD7-P)") (class "Default")
      (node (ref "C6") (pin "1") (pinfunction "1_1") (pintype "passive"))
      (node (ref "PAD7") (pin "1") (pinfunction "P_1") (pintype "passive"))
      (node (ref "R12") (pin "1") (pinfunction "1_1") (pintype "passive"))
      (node (ref "R4") (pin "1") (pinfunction "1_1") (pintype "passive"))
    )
    (net (code "51") (name "Net-(PAD8-P)") (class "Default")
      (node (ref "C8") (pin "1") (pinfunction "1_1") (pintype "passive"))
      (node (ref "PAD8") (pin "1") (pinfunction "P_1") (pintype "passive"))
      (node (ref "R17") (pin "1") (pinfunction "1_1") (pintype "passive"))
      (node (ref "R5") (pin "1") (pinfunction "1_1") (pintype "passive"))
    )
    (net (code "52") (name "Net-(PAD27-P)") (class "Default")
      (node (ref "C14") (pin "1") (pinfunction "1_1") (pintype "passive"))
      (node (ref "PAD27") (pin "1") (pinfunction "P_1") (pintype "passive"))
      (node (ref "R11") (pin "1") (pinfunction "1_1") (pintype "passive"))
    )
    (net (code "53") (name "Net-(PAD28-P)") (class "Default")
      (node (ref "C16") (pin "1") (pinfunction "1_1") (pintype "passive"))
      (node (ref "PAD28") (pin "1") (pinfunction "P_1") (pintype "passive"))
      (node (ref "R13") (pin "1") (pinfunction "1_1") (pintype "passive"))
    )
    (net (code "54") (name "Net-(PAD29-P)") (class "Default")
      (node (ref "C18") (pin "1") (pinfunction "1_1") (pintype "passive"))
      (node (ref "PAD29") (pin "1") (pinfunction "P_1") (pintype "passive"))
      (node (ref "R14") (pin "1") (pinfunction "1_1") (pintype "passive"))
    )
    (net (code "55") (name "Net-(PAD30-P)") (class "Default")
      (node (ref "C20") (pin "1") (pinfunction "1_1") (pintype "passive"))
      (node (ref "PAD30") (pin "1") (pinfunction "P_1") (pintype "passive"))
      (node (ref "R15") (pin "1") (pinfunction "1_1") (pintype "passive"))
    )
    (net (code "56") (name "Net-(PAD35-P)") (class "Default")
      (node (ref "PAD35") (pin "1") (pinfunction "P_1") (pintype "passive"))
      (node (ref "R19") (pin "1") (pinfunction "1_1") (pintype "passive"))
    )
    (net (code "57") (name "Net-(PAD36-P)") (class "Default")
      (node (ref "PAD36") (pin "1") (pinfunction "P_1") (pintype "passive"))
      (node (ref "R20") (pin "1") (pinfunction "1_1") (pintype "passive"))
    )
    (net (code "58") (name "Net-(Q1-D)") (class "Default")
      (node (ref "Q1") (pin "3") (pinfunction "D_3") (pintype "passive"))
      (node (ref "X3") (pin "1") (pinfunction ">NAME$_1") (pintype "bidirectional"))
    )
    (net (code "59") (name "Net-(Q1-G)") (class "Default")
      (node (ref "Q1") (pin "1") (pinfunction "G_1") (pintype "passive"))
      (node (ref "R21") (pin "2") (pinfunction "2_2") (pintype "passive"))
    )
    (net (code "60") (name "Net-(Q1-S)") (class "Default")
      (node (ref "Q1") (pin "2") (pinfunction "S_2") (pintype "passive"))
      (node (ref "Q2") (pin "2") (pinfunction "S_2") (pintype "passive"))
      (node (ref "Q3") (pin "2") (pinfunction "S_2") (pintype "passive"))
      (node (ref "Q4") (pin "2") (pinfunction "S_2") (pintype "passive"))
      (node (ref "R22") (pin "1") (pinfunction "1_1") (pintype "passive"))
      (node (ref "R24") (pin "1") (pinfunction "1_1") (pintype "passive"))
      (node (ref "R26") (pin "1") (pinfunction "1_1") (pintype "passive"))
      (node (ref "R28") (pin "1") (pinfunction "1_1") (pintype "passive"))
      (node (ref "R51") (pin "1") (pinfunction "1_1") (pintype "passive"))
      (node (ref "X3") (pin "4") (pinfunction ">NAME$_4") (pintype "bidirectional"))
      (node (ref "X3") (pin "6") (pinfunction ">NAME$_6") (pintype "bidirectional"))
    )
    (net (code "61") (name "Net-(Q2-D)") (class "Default")
      (node (ref "Q2") (pin "3") (pinfunction "D_3") (pintype "passive"))
      (node (ref "X3") (pin "2") (pinfunction ">NAME$_2") (pintype "bidirectional"))
    )
    (net (code "62") (name "Net-(Q2-G)") (class "Default")
      (node (ref "Q2") (pin "1") (pinfunction "G_1") (pintype "passive"))
      (node (ref "R23") (pin "2") (pinfunction "2_2") (pintype "passive"))
    )
    (net (code "63") (name "Net-(Q3-D)") (class "Default")
      (node (ref "Q3") (pin "3") (pinfunction "D_3") (pintype "passive"))
      (node (ref "X3") (pin "5") (pinfunction ">NAME$_5") (pintype "bidirectional"))
    )
    (net (code "64") (name "Net-(Q3-G)") (class "Default")
      (node (ref "Q3") (pin "1") (pinfunction "G_1") (pintype "passive"))
      (node (ref "R25") (pin "2") (pinfunction "2_2") (pintype "passive"))
    )
    (net (code "65") (name "Net-(Q4-D)") (class "Default")
      (node (ref "Q4") (pin "3") (pinfunction "D_3") (pintype "passive"))
      (node (ref "X3") (pin "3") (pinfunction ">NAME$_3") (pintype "bidirectional"))
    )
    (net (code "66") (name "Net-(Q4-G)") (class "Default")
      (node (ref "Q4") (pin "1") (pinfunction "G_1") (pintype "passive"))
      (node (ref "R27") (pin "2") (pinfunction "2_2") (pintype "passive"))
    )
    (net (code "67") (name "Net-(Q5-D)") (class "Default")
      (node (ref "Q5") (pin "3") (pinfunction "D_3") (pintype "passive"))
      (node (ref "X1") (pin "8") (pinfunction ">NAME$_8") (pintype "bidirectional"))
    )
    (net (code "68") (name "Net-(Q5-G)") (class "Default")
      (node (ref "Q5") (pin "1") (pinfunction "G_1") (pintype "passive"))
      (node (ref "R29") (pin "2") (pinfunction "2_2") (pintype "passive"))
    )
    (net (code "69") (name "Net-(Q5-S)") (class "Default")
      (node (ref "Q5") (pin "2") (pinfunction "S_2") (pintype "passive"))
      (node (ref "Q6") (pin "2") (pinfunction "S_2") (pintype "passive"))
      (node (ref "R30") (pin "1") (pinfunction "1_1") (pintype "passive"))
      (node (ref "R32") (pin "1") (pinfunction "1_1") (pintype "passive"))
      (node (ref "R50") (pin "1") (pinfunction "1_1") (pintype "passive"))
      (node (ref "X1") (pin "7") (pinfunction ">NAME$_7") (pintype "bidirectional"))
    )
    (net (code "70") (name "Net-(Q6-D)") (class "Default")
      (node (ref "Q6") (pin "3") (pinfunction "D_3") (pintype "passive"))
      (node (ref "X1") (pin "6") (pinfunction ">NAME$_6") (pintype "bidirectional"))
    )
    (net (code "71") (name "Net-(Q6-G)") (class "Default")
      (node (ref "Q6") (pin "1") (pinfunction "G_1") (pintype "passive"))
      (node (ref "R31") (pin "2") (pinfunction "2_2") (pintype "passive"))
    )
    (net (code "72") (name "Net-(SW1-P)") (class "Default")
      (node (ref "R16") (pin "2") (pinfunction "2_2") (pintype "passive"))
      (node (ref "SW1") (pin "1") (pinfunction "P_1") (pintype "passive"))
    )
    (net (code "73") (name "Net-(SW2-P)") (class "Default")
      (node (ref "R18") (pin "2") (pinfunction "2_2") (pintype "passive"))
      (node (ref "SW2") (pin "1") (pinfunction "P_1") (pintype "passive"))
    )
    (net (code "74") (name "Net-(X1A->NAME$)") (class "Default")
      (node (ref "R52") (pin "2") (pinfunction "2_2") (pintype "passive"))
      (node (ref "X1") (pin "1") (pinfunction ">NAME$_1") (pintype "bidirectional"))
    )
    (net (code "75") (name "Net-(X1B->NAME$)") (class "Default")
      (node (ref "R53") (pin "2") (pinfunction "2_2") (pintype "passive"))
      (node (ref "X1") (pin "2") (pinfunction ">NAME$_2") (pintype "bidirectional"))
    )
    (net (code "76") (name "Net-(X1C->NAME$)") (class "Default")
      (node (ref "R54") (pin "2") (pinfunction "2_2") (pintype "passive"))
      (node (ref "X1") (pin "3") (pinfunction ">NAME$_3") (pintype "bidirectional"))
    )
    (net (code "77") (name "Net-(X1D->NAME$)") (class "Default")
      (node (ref "R55") (pin "2") (pinfunction "2_2") (pintype "passive"))
      (node (ref "X1") (pin "4") (pinfunction ">NAME$_4") (pintype "bidirectional"))
    )
    (net (code "78") (name "Net-(X2B->NAME$)") (class "Default")
      (node (ref "R45") (pin "2") (pinfunction "2_2") (pintype "passive"))
      (node (ref "X2") (pin "2") (pinfunction ">NAME$_2") (pintype "bidirectional"))
    )
    (net (code "79") (name "Net-(X2D->NAME$)") (class "Default")
      (node (ref "R42") (pin "1") (pinfunction "1_1") (pintype "passive"))
      (node (ref "X2") (pin "4") (pinfunction ">NAME$_4") (pintype "bidirectional"))
    )
    (net (code "80") (name "Net-(X2E->NAME$)") (class "Default")
      (node (ref "R43") (pin "1") (pinfunction "1_1") (pintype "passive"))
      (node (ref "X2") (pin "5") (pinfunction ">NAME$_5") (pintype "bidirectional"))
    )
  )
)
